# modular_pcb3.net
KiCad netlist of a schematic drawn in EAGLE
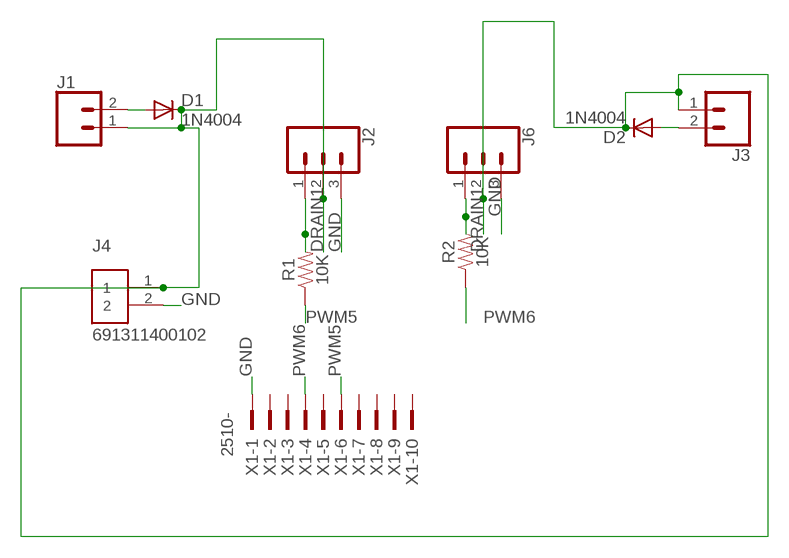
[diagram p0: schematic, sheet 1]

(export (version "E")
  (design (tool "Eeschema 10.0.6"))
  (components
    (comp (ref "D1")
      (value "1N4004")
      (footprint "eagle-import:DO41-10")
      (libsource (lib "eagle-import") (part "1N4004"))
    )
    (comp (ref "D2")
      (value "1N4004")
      (footprint "eagle-import:DO41-10")
      (libsource (lib "eagle-import") (part "1N4004"))
    )
    (comp (ref "J1")
      (value "CONN_02")
      (footprint "eagle-import:1X02")
      (libsource (lib "eagle-import") (part "CONN_02"))
    )
    (comp (ref "J2")
      (value "455-1750-1-ND")
      (footprint "eagle-import:1X03")
      (libsource (lib "eagle-import") (part "CONN_03"))
    )
    (comp (ref "J3")
      (value "CONN_02")
      (footprint "eagle-import:1X02")
      (libsource (lib "eagle-import") (part "CONN_02"))
    )
    (comp (ref "J4")
      (value "691311400102")
      (footprint "eagle-import:TERMINALBLOCK_PLUGGABLE-2-7.62MM")
      (fields
        (field (name "DIGIKEY_PART_NO") "732-2823-ND")
        (field (name "MANUFACTURER") "WURTH ELEKTRONIK")
        (field (name "CREATED_BY") "PCBLayout.com")
      )
      (libsource (lib "eagle-import") (part "691311400102"))
    )
    (comp (ref "J6")
      (value "455-1750-1-ND")
      (footprint "eagle-import:1X03")
      (libsource (lib "eagle-import") (part "CONN_03"))
    )
    (comp (ref "R1")
      (value "10K")
      (footprint "eagle-import:0402-TIGHT")
      (libsource (lib "eagle-import") (part "10KOHM-0402-1/10W-0.1%"))
    )
    (comp (ref "R2")
      (value "10K")
      (footprint "eagle-import:0402-TIGHT")
      (libsource (lib "eagle-import") (part "10KOHM-0402-1/10W-0.1%"))
    )
    (comp (ref "X1")
      (value "2510-")
      (footprint "eagle-import:PAK100_2500-10")
      (fields (field (name "MF") "3M") (field (name "MPN") "2510-6002UB"))
      (libsource (lib "eagle-import") (part "2510-"))
    )
  )
  (nets
    (net (code "1") (name "/DRAIN1") (class "Default")
      (node (ref "D1") (pin "C") (pinfunction "C_C") (pintype "passive"))
      (node (ref "D2") (pin "C") (pinfunction "C_C") (pintype "passive"))
      (node (ref "J1") (pin "1") (pinfunction "1_1") (pintype "passive"))
      (node (ref "J2") (pin "2") (pinfunction "2_2") (pintype "passive"))
      (node (ref "J3") (pin "1") (pinfunction "1_1") (pintype "passive"))
      (node (ref "J4") (pin "1") (pinfunction "1_1") (pintype "passive"))
      (node (ref "J6") (pin "2") (pinfunction "2_2") (pintype "passive"))
    )
    (net (code "2") (name "/GND") (class "Default")
      (node (ref "J2") (pin "3") (pinfunction "3_3") (pintype "passive"))
      (node (ref "J4") (pin "2") (pinfunction "2_2") (pintype "passive"))
      (node (ref "J6") (pin "3") (pinfunction "3_3") (pintype "passive"))
      (node (ref "X1") (pin "1") (pinfunction "KL_1") (pintype "passive"))
    )
    (net (code "3") (name "/PWM5") (class "Default")
      (node (ref "R1") (pin "1") (pinfunction "1_1") (pintype "passive"))
      (node (ref "X1") (pin "6") (pinfunction "KL_6") (pintype "passive"))
    )
    (net (code "4") (name "/PWM6") (class "Default")
      (node (ref "R2") (pin "1") (pinfunction "1_1") (pintype "passive"))
      (node (ref "X1") (pin "4") (pinfunction "KL_4") (pintype "passive"))
    )
    (net (code "5") (name "Net-(D1-PadA)") (class "Default")
      (node (ref "D1") (pin "A") (pinfunction "A_A") (pintype "passive"))
      (node (ref "J1") (pin "2") (pinfunction "2_2") (pintype "passive"))
    )
    (net (code "6") (name "Net-(D2-PadA)") (class "Default")
      (node (ref "D2") (pin "A") (pinfunction "A_A") (pintype "passive"))
      (node (ref "J3") (pin "2") (pinfunction "2_2") (pintype "passive"))
    )
    (net (code "7") (name "Net-(J2-Pad1)") (class "Default")
      (node (ref "J2") (pin "1") (pinfunction "1_1") (pintype "passive"))
      (node (ref "R1") (pin "2") (pinfunction "2_2") (pintype "passive"))
    )
    (net (code "8") (name "Net-(J6-Pad1)") (class "Default")
      (node (ref "J6") (pin "1") (pinfunction "1_1") (pintype "passive"))
      (node (ref "R2") (pin "2") (pinfunction "2_2") (pintype "passive"))
    )
    (net (code "9") (name "unconnected-(X1B-KL-Pad10)") (class "Default")
      (node (ref "X1") (pin "10") (pinfunction "KL_10") (pintype "passive"))
    )
    (net (code "10") (name "unconnected-(X1C-KL-Pad2)") (class "Default")
      (node (ref "X1") (pin "2") (pinfunction "KL_2") (pintype "passive"))
    )
    (net (code "11") (name "unconnected-(X1D-KL-Pad3)") (class "Default")
      (node (ref "X1") (pin "3") (pinfunction "KL_3") (pintype "passive"))
    )
    (net (code "12") (name "unconnected-(X1F-KL-Pad5)") (class "Default")
      (node (ref "X1") (pin "5") (pinfunction "KL_5") (pintype "passive"))
    )
    (net (code "13") (name "unconnected-(X1H-KL-Pad7)") (class "Default")
      (node (ref "X1") (pin "7") (pinfunction "KL_7") (pintype "passive"))
    )
    (net (code "14") (name "unconnected-(X1I-KL-Pad8)") (class "Default")
      (node (ref "X1") (pin "8") (pinfunction "KL_8") (pintype "passive"))
    )
    (net (code "15") (name "unconnected-(X1J-KL-Pad9)") (class "Default")
      (node (ref "X1") (pin "9") (pinfunction "KL_9") (pintype "passive"))
    )
  )
)
